# Emulator.net
KiCad netlist of a schematic drawn in EAGLE
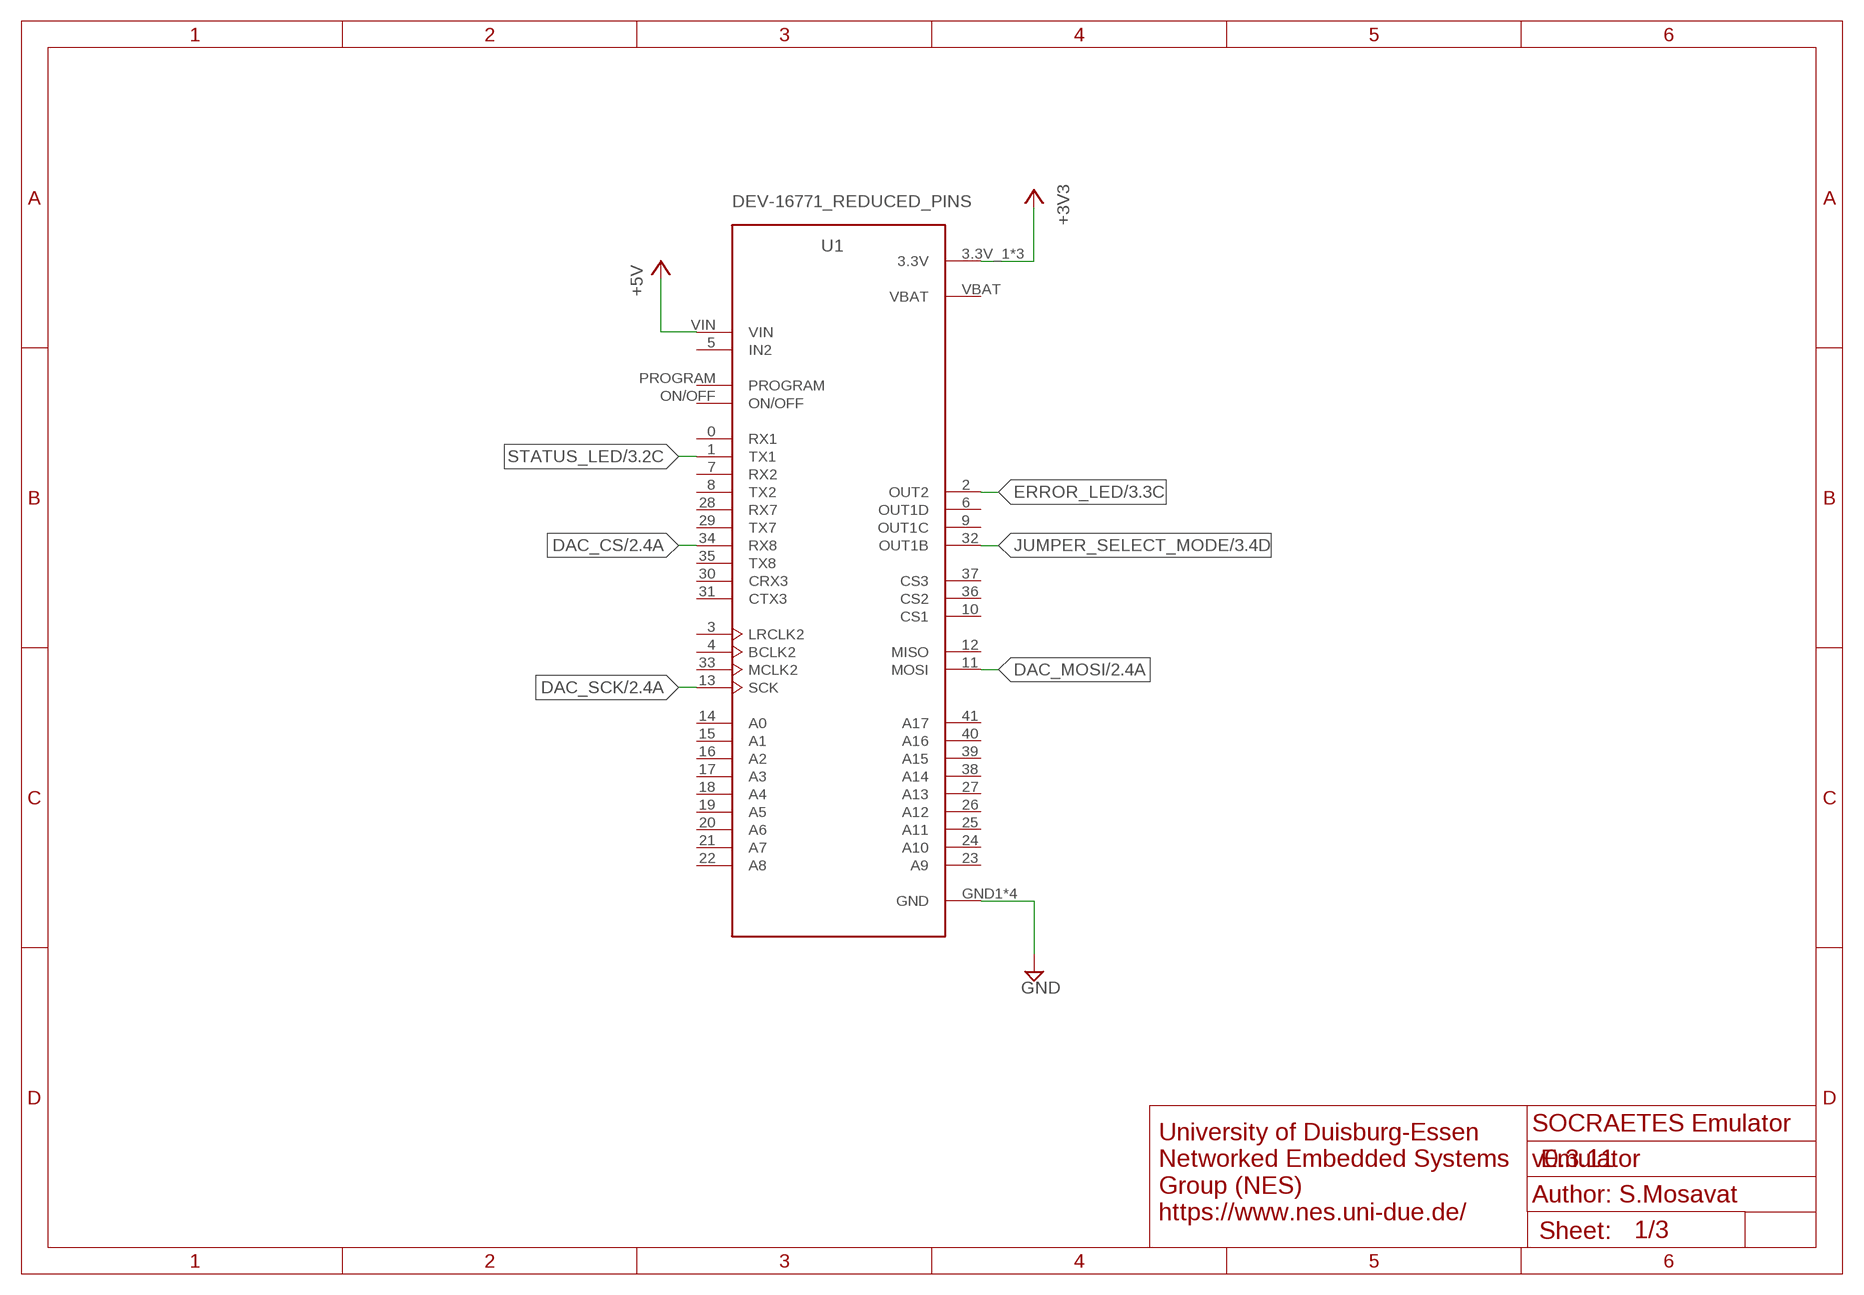
[diagram p0: schematic, sheet 1]
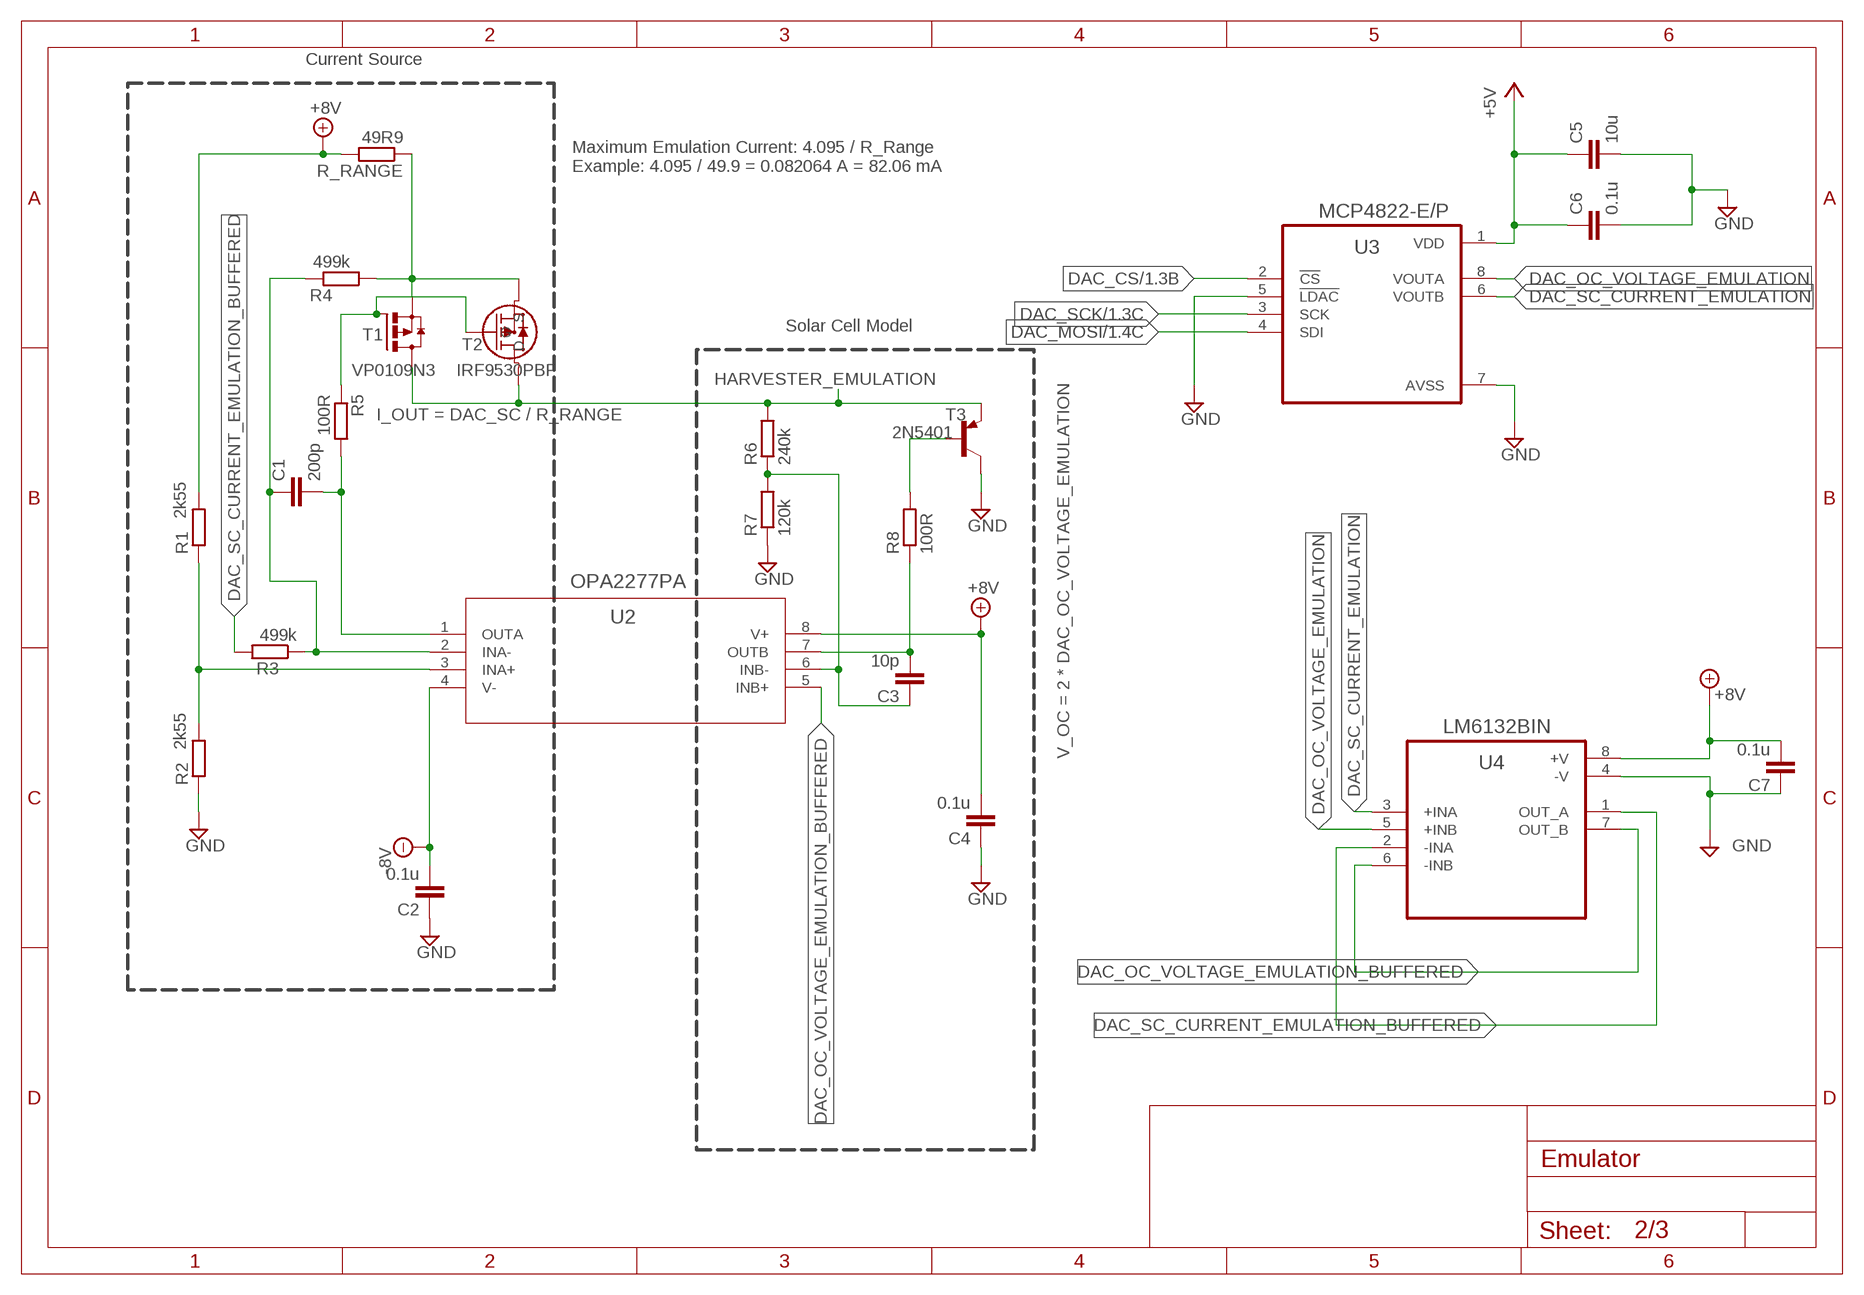
[diagram p1: schematic, sheet 2]
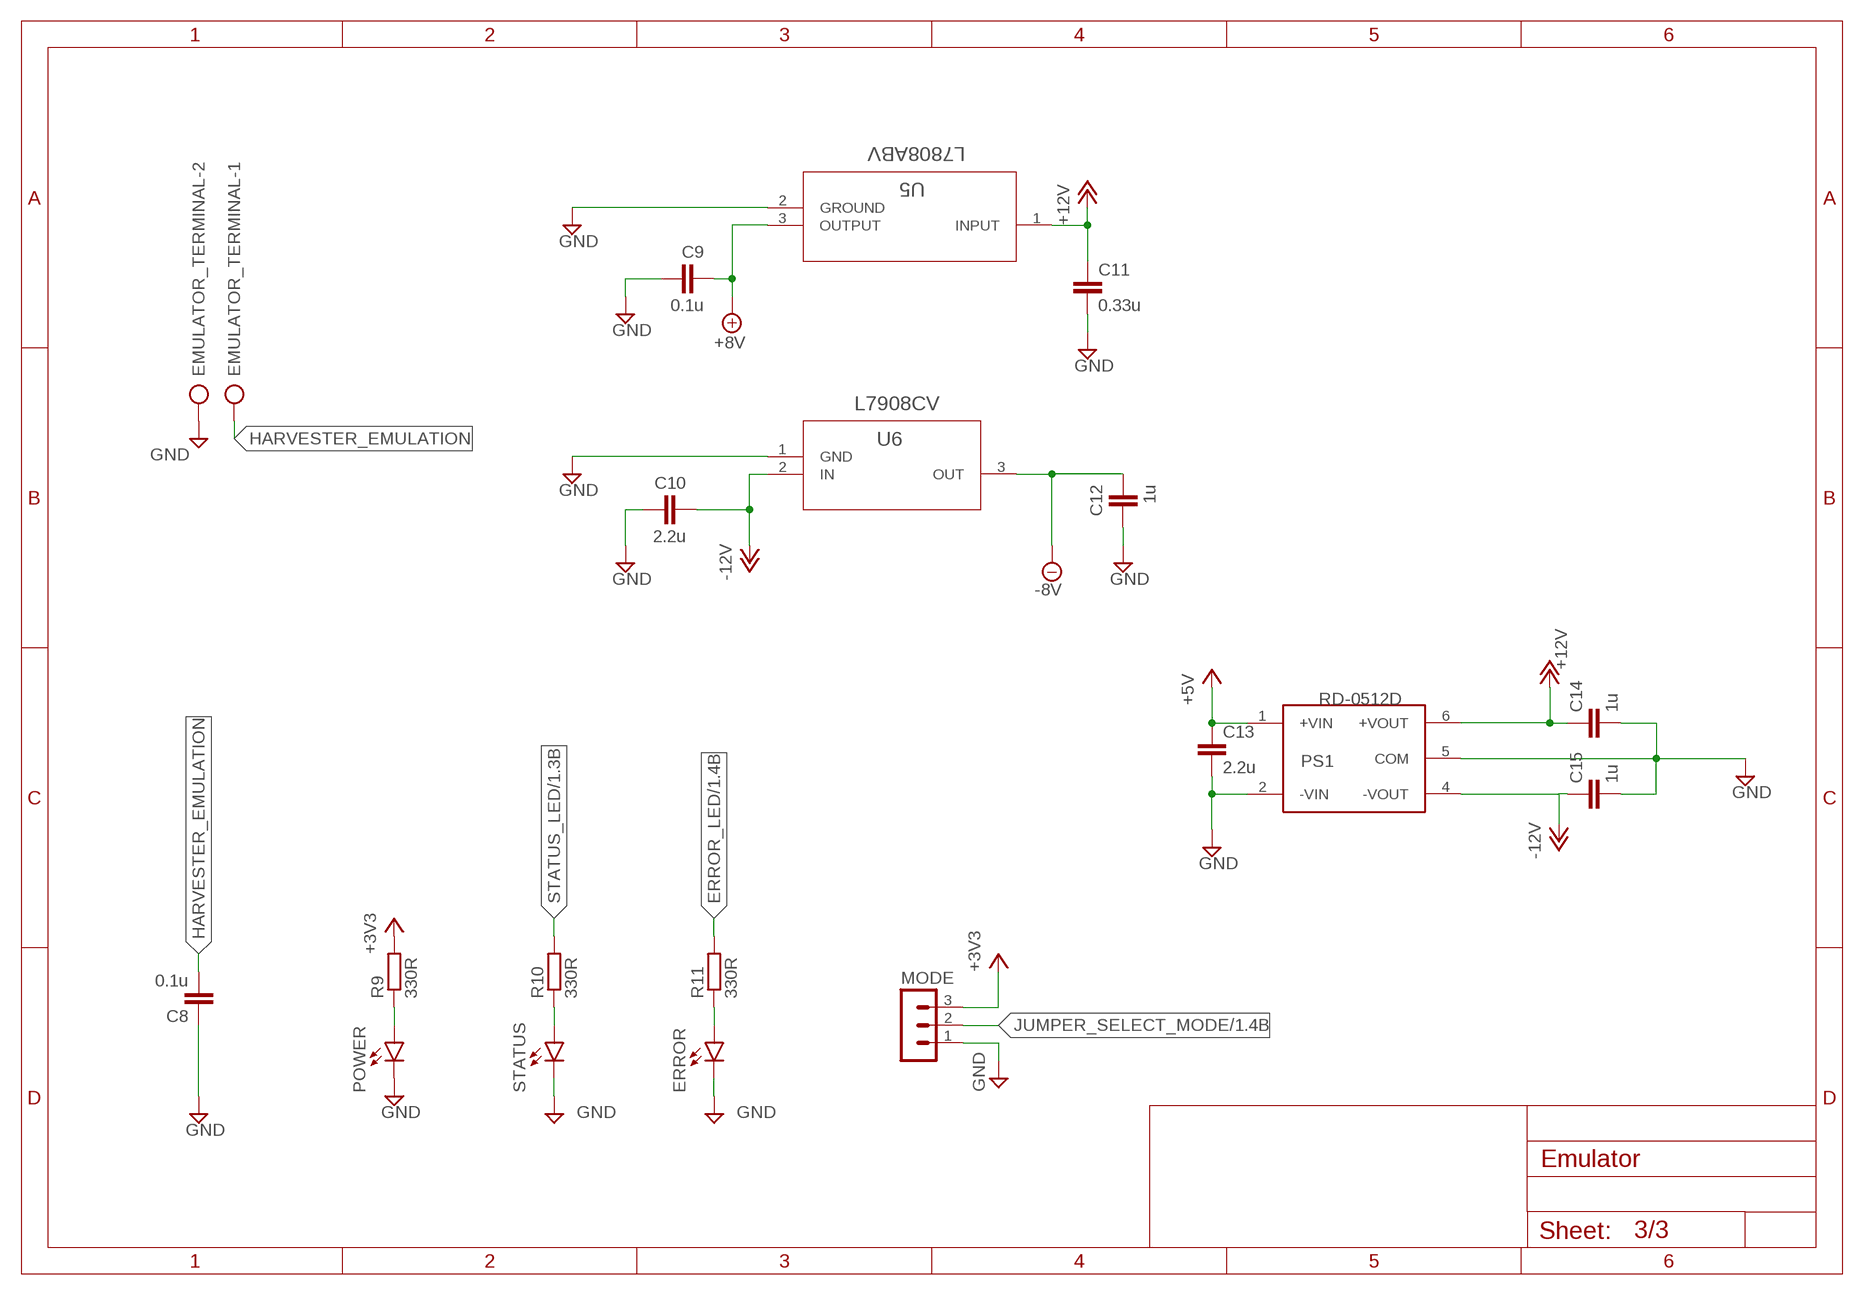
[diagram p2: schematic, sheet 3]

(export (version "E")
  (design (tool "Eeschema 10.0.6"))
  (components
    (comp (ref "U1")
      (value "DEV-16771_REDUCED_PINS")
      (footprint "eagle-import:MODULE_DEV-16771_REDUCED_PINS")
      (libsource (lib "eagle-import") (part "DEV-16771_REDUCED_PINS"))
    )
    (comp (ref "C1")
      (value "200p")
      (footprint "eagle-import:C025-024X044")
      (libsource (lib "eagle-import") (part "C-EU025-024X044"))
    )
    (comp (ref "C2")
      (value "0.1u")
      (footprint "eagle-import:C025-024X044")
      (libsource (lib "eagle-import") (part "C-EU025-024X044"))
    )
    (comp (ref "C3")
      (value "10p")
      (footprint "eagle-import:C025-024X044")
      (libsource (lib "eagle-import") (part "C-EU025-024X044"))
    )
    (comp (ref "C4")
      (value "0.1u")
      (footprint "eagle-import:C025-024X044")
      (libsource (lib "eagle-import") (part "C-EU025-024X044"))
    )
    (comp (ref "C5")
      (value "10u")
      (footprint "eagle-import:C025-024X044")
      (libsource (lib "eagle-import") (part "C-EU025-024X044"))
    )
    (comp (ref "C6")
      (value "0.1u")
      (footprint "eagle-import:C025-024X044")
      (libsource (lib "eagle-import") (part "C-EU025-024X044"))
    )
    (comp (ref "C7")
      (value "0.1u")
      (footprint "eagle-import:C025-024X044")
      (libsource (lib "eagle-import") (part "C-EU025-024X044"))
    )
    (comp (ref "R1")
      (value "2k55")
      (footprint "eagle-import:0207_10")
      (libsource (lib "eagle-import") (part "R-EU_0207/10"))
    )
    (comp (ref "R2")
      (value "2k55")
      (footprint "eagle-import:0207_10")
      (libsource (lib "eagle-import") (part "R-EU_0207/10"))
    )
    (comp (ref "R3")
      (value "499k")
      (footprint "eagle-import:0207_10")
      (libsource (lib "eagle-import") (part "R-EU_0207/10"))
    )
    (comp (ref "R4")
      (value "499k")
      (footprint "eagle-import:0207_10")
      (libsource (lib "eagle-import") (part "R-EU_0207/10"))
    )
    (comp (ref "R5")
      (value "100R")
      (footprint "eagle-import:0207_10")
      (libsource (lib "eagle-import") (part "R-EU_0207/10"))
    )
    (comp (ref "R6")
      (value "240k")
      (footprint "eagle-import:0207_10")
      (libsource (lib "eagle-import") (part "R-EU_0207/10"))
    )
    (comp (ref "R7")
      (value "120k")
      (footprint "eagle-import:0207_10")
      (libsource (lib "eagle-import") (part "R-EU_0207/10"))
    )
    (comp (ref "R8")
      (value "100R")
      (footprint "eagle-import:0207_10")
      (libsource (lib "eagle-import") (part "R-EU_0207/10"))
    )
    (comp (ref "R_RANGE")
      (value "49R9")
      (footprint "eagle-import:0207_10")
      (libsource (lib "eagle-import") (part "R-EU_0207/10"))
    )
    (comp (ref "T1")
      (value "VP0109N3")
      (footprint "eagle-import:TO92-SGD")
      (libsource (lib "eagle-import") (part "VP0109N3"))
    )
    (comp (ref "T2")
      (value "IRF9530PBF")
      (footprint "eagle-import:TO220AB_VIS")
      (fields (field (name "COPYRIGHT") "Copyright (C) 2023 Ultra Librarian. All rights reserved."))
      (libsource (lib "eagle-import") (part "IRF9530PBF"))
    )
    (comp (ref "T3")
      (value "2N5401")
      (footprint "eagle-import:TO92-EBC")
      (libsource (lib "eagle-import") (part "-PNP-TO92-EBC2N5401"))
    )
    (comp (ref "U2")
      (value "OPA2277PA")
      (footprint "eagle-import:P8")
      (fields
        (field (name "GENERIC_PART_NUMBER") "OPA2277")
        (field (name "MANUFACTURER") "Texas Instruments")
      )
      (libsource (lib "eagle-import") (part "OPA2277PA"))
    )
    (comp (ref "U3")
      (value "MCP4822-E/P")
      (footprint "eagle-import:DIP787W46P254L927H533Q8")
      (fields (field (name "MF") "Microchip"))
      (libsource (lib "eagle-import") (part "MCP4822-E/P"))
    )
    (comp (ref "U4")
      (value "LM6132BIN")
      (footprint "eagle-import:DIP794W45P254L959H508Q8")
      (fields
        (field (name "DIGI-KEY_PART_NUMBER") "LM6132BIN/NOPB-ND")
        (field (name "MF") "Texas Instruments")
        (field (name "MP") "LM6132BIN/NOPB")
      )
      (libsource (lib "eagle-import") (part "LM6132BIN"))
    )
    (comp (ref "C8")
      (value "0.1u")
      (footprint "eagle-import:C025-024X044")
      (libsource (lib "eagle-import") (part "C-EU025-024X044"))
    )
    (comp (ref "C9")
      (value "0.1u")
      (footprint "eagle-import:C025-024X044")
      (libsource (lib "eagle-import") (part "C-EU025-024X044"))
    )
    (comp (ref "C10")
      (value "2.2u")
      (footprint "eagle-import:C025-024X044")
      (libsource (lib "eagle-import") (part "C-EU025-024X044"))
    )
    (comp (ref "C11")
      (value "0.33u")
      (footprint "eagle-import:C025-024X044")
      (libsource (lib "eagle-import") (part "C-EU025-024X044"))
    )
    (comp (ref "C12")
      (value "1u")
      (footprint "eagle-import:C025-024X044")
      (libsource (lib "eagle-import") (part "C-EU025-024X044"))
    )
    (comp (ref "C13")
      (value "2.2u")
      (footprint "eagle-import:C025-024X044")
      (libsource (lib "eagle-import") (part "C-EU025-024X044"))
    )
    (comp (ref "C14")
      (value "1u")
      (footprint "eagle-import:C025-024X044")
      (libsource (lib "eagle-import") (part "C-EU025-024X044"))
    )
    (comp (ref "C15")
      (value "1u")
      (footprint "eagle-import:C025-024X044")
      (libsource (lib "eagle-import") (part "C-EU025-024X044"))
    )
    (comp (ref "EMULATOR_TERMINAL")
      (value "AK300/2")
      (footprint "eagle-import:AK300_2")
      (libsource (lib "eagle-import") (part "AK300/2"))
    )
    (comp (ref "ERROR")
      (value "LED5MM")
      (footprint "eagle-import:LED5MM")
      (libsource (lib "eagle-import") (part "LED5MM"))
    )
    (comp (ref "MODE")
      (value "MA03-1")
      (footprint "eagle-import:MA03-1")
      (libsource (lib "eagle-import") (part "MA03-1"))
    )
    (comp (ref "POWER")
      (value "LED5MM")
      (footprint "eagle-import:LED5MM")
      (libsource (lib "eagle-import") (part "LED5MM"))
    )
    (comp (ref "PS1")
      (value "RD-0512D")
      (footprint "eagle-import:CONV_RD-0512D")
      (fields (field (name "MF") "Recom Power"))
      (libsource (lib "eagle-import") (part "RD-0512D"))
    )
    (comp (ref "R9")
      (value "330R")
      (footprint "eagle-import:0207_10")
      (libsource (lib "eagle-import") (part "R-EU_0207/10"))
    )
    (comp (ref "R10")
      (value "330R")
      (footprint "eagle-import:0207_10")
      (libsource (lib "eagle-import") (part "R-EU_0207/10"))
    )
    (comp (ref "R11")
      (value "330R")
      (footprint "eagle-import:0207_10")
      (libsource (lib "eagle-import") (part "R-EU_0207/10"))
    )
    (comp (ref "STATUS")
      (value "LED5MM")
      (footprint "eagle-import:LED5MM")
      (libsource (lib "eagle-import") (part "LED5MM"))
    )
    (comp (ref "U5")
      (value "L7808ABV")
      (footprint "eagle-import:TO-220_STM")
      (libsource (lib "eagle-import") (part "L7808ABV"))
    )
    (comp (ref "U6")
      (value "L7908CV")
      (footprint "eagle-import:TO-220_STM")
      (libsource (lib "eagle-import") (part "L7908CV"))
    )
  )
  (nets
    (net (code "1") (name "+3V3") (class "Default")
      (node (ref "MODE") (pin "3") (pinfunction "3_3") (pintype "passive"))
      (node (ref "R9") (pin "2") (pinfunction "2_2") (pintype "passive"))
      (node (ref "U1") (pin "3.3V_1") (pinfunction "3.3V_3.3V_1") (pintype "power_in"))
      (node (ref "U1") (pin "3.3V_2") (pinfunction "3.3V_3.3V_2") (pintype "power_in"))
      (node (ref "U1") (pin "3.3V_3") (pinfunction "3.3V_3.3V_3") (pintype "power_in"))
    )
    (net (code "2") (name "+5V") (class "Default")
      (node (ref "C13") (pin "1") (pinfunction "1_1") (pintype "passive"))
      (node (ref "C5") (pin "1") (pinfunction "1_1") (pintype "passive"))
      (node (ref "C6") (pin "1") (pinfunction "1_1") (pintype "passive"))
      (node (ref "PS1") (pin "1") (pinfunction "+VIN_1") (pintype "input"))
      (node (ref "U1") (pin "VIN") (pinfunction "VIN_VIN") (pintype "input"))
      (node (ref "U3") (pin "1") (pinfunction "VDD_1") (pintype "power_in"))
    )
    (net (code "3") (name "+8V") (class "Default")
      (node (ref "C4") (pin "2") (pinfunction "2_2") (pintype "passive"))
      (node (ref "C7") (pin "2") (pinfunction "2_2") (pintype "passive"))
      (node (ref "C9") (pin "2") (pinfunction "2_2") (pintype "passive"))
      (node (ref "R1") (pin "2") (pinfunction "2_2") (pintype "passive"))
      (node (ref "R_RANGE") (pin "2") (pinfunction "2_2") (pintype "passive"))
      (node (ref "U2") (pin "8") (pinfunction "V+_8") (pintype "power_in"))
      (node (ref "U4") (pin "8") (pinfunction "+V_8") (pintype "power_in"))
      (node (ref "U5") (pin "3") (pinfunction "OUTPUT_3") (pintype "output"))
    )
    (net (code "4") (name "+12V") (class "Default")
      (node (ref "C11") (pin "1") (pinfunction "1_1") (pintype "passive"))
      (node (ref "C14") (pin "1") (pinfunction "1_1") (pintype "passive"))
      (node (ref "PS1") (pin "6") (pinfunction "+VOUT_6") (pintype "output"))
      (node (ref "U5") (pin "1") (pinfunction "INPUT_1") (pintype "input"))
    )
    (net (code "5") (name "-8V") (class "Default")
      (node (ref "C12") (pin "2") (pinfunction "2_2") (pintype "passive"))
      (node (ref "C2") (pin "2") (pinfunction "2_2") (pintype "passive"))
      (node (ref "U2") (pin "4") (pinfunction "V-_4") (pintype "power_in"))
      (node (ref "U6") (pin "3") (pinfunction "OUT_3") (pintype "power_in"))
    )
    (net (code "6") (name "-12V") (class "Default")
      (node (ref "C10") (pin "2") (pinfunction "2_2") (pintype "passive"))
      (node (ref "C15") (pin "1") (pinfunction "1_1") (pintype "passive"))
      (node (ref "PS1") (pin "4") (pinfunction "-VOUT_4") (pintype "output"))
      (node (ref "U6") (pin "2") (pinfunction "IN_2") (pintype "power_in"))
    )
    (net (code "7") (name "DAC_CS") (class "Default")
      (node (ref "U1") (pin "34") (pinfunction "RX8_34") (pintype "bidirectional"))
      (node (ref "U3") (pin "2") (pinfunction "~{CS}_2") (pintype "input"))
    )
    (net (code "8") (name "DAC_MOSI") (class "Default")
      (node (ref "U1") (pin "11") (pinfunction "MOSI_11") (pintype "bidirectional"))
      (node (ref "U3") (pin "4") (pinfunction "SDI_4") (pintype "input"))
    )
    (net (code "9") (name "DAC_OC_VOLTAGE_EMULATION") (class "Default")
      (node (ref "U3") (pin "8") (pinfunction "VOUTA_8") (pintype "output"))
      (node (ref "U4") (pin "5") (pinfunction "+INB_5") (pintype "input"))
    )
    (net (code "10") (name "DAC_OC_VOLTAGE_EMULATION_BUFFERED") (class "Default")
      (node (ref "U2") (pin "5") (pinfunction "INB+_5") (pintype "input"))
      (node (ref "U4") (pin "6") (pinfunction "-INB_6") (pintype "input"))
      (node (ref "U4") (pin "7") (pinfunction "OUT_B_7") (pintype "output"))
    )
    (net (code "11") (name "DAC_SCK") (class "Default")
      (node (ref "U1") (pin "13") (pinfunction "SCK_13") (pintype "bidirectional"))
      (node (ref "U3") (pin "3") (pinfunction "SCK_3") (pintype "input"))
    )
    (net (code "12") (name "DAC_SC_CURRENT_EMULATION") (class "Default")
      (node (ref "U3") (pin "6") (pinfunction "VOUTB_6") (pintype "output"))
      (node (ref "U4") (pin "3") (pinfunction "+INA_3") (pintype "input"))
    )
    (net (code "13") (name "DAC_SC_CURRENT_EMULATION_BUFFERED") (class "Default")
      (node (ref "R3") (pin "2") (pinfunction "2_2") (pintype "passive"))
      (node (ref "U4") (pin "1") (pinfunction "OUT_A_1") (pintype "output"))
      (node (ref "U4") (pin "2") (pinfunction "-INA_2") (pintype "input"))
    )
    (net (code "14") (name "ERROR_LED") (class "Default")
      (node (ref "R11") (pin "2") (pinfunction "2_2") (pintype "passive"))
      (node (ref "U1") (pin "2") (pinfunction "OUT2_2") (pintype "output"))
    )
    (net (code "15") (name "GND") (class "Default")
      (node (ref "C10") (pin "1") (pinfunction "1_1") (pintype "passive"))
      (node (ref "C11") (pin "2") (pinfunction "2_2") (pintype "passive"))
      (node (ref "C12") (pin "1") (pinfunction "1_1") (pintype "passive"))
      (node (ref "C13") (pin "2") (pinfunction "2_2") (pintype "passive"))
      (node (ref "C14") (pin "2") (pinfunction "2_2") (pintype "passive"))
      (node (ref "C15") (pin "2") (pinfunction "2_2") (pintype "passive"))
      (node (ref "C2") (pin "1") (pinfunction "1_1") (pintype "passive"))
      (node (ref "C4") (pin "1") (pinfunction "1_1") (pintype "passive"))
      (node (ref "C5") (pin "2") (pinfunction "2_2") (pintype "passive"))
      (node (ref "C6") (pin "2") (pinfunction "2_2") (pintype "passive"))
      (node (ref "C7") (pin "1") (pinfunction "1_1") (pintype "passive"))
      (node (ref "C8") (pin "1") (pinfunction "1_1") (pintype "passive"))
      (node (ref "C9") (pin "1") (pinfunction "1_1") (pintype "passive"))
      (node (ref "EMULATOR_TERMINAL") (pin "2") (pinfunction "KL_2") (pintype "passive"))
      (node (ref "ERROR") (pin "K") (pinfunction "C_K") (pintype "passive"))
      (node (ref "MODE") (pin "1") (pinfunction "1_1") (pintype "passive"))
      (node (ref "POWER") (pin "K") (pinfunction "C_K") (pintype "passive"))
      (node (ref "PS1") (pin "2") (pinfunction "-VIN_2") (pintype "input"))
      (node (ref "PS1") (pin "5") (pinfunction "COM_5") (pintype "power_in"))
      (node (ref "R2") (pin "1") (pinfunction "1_1") (pintype "passive"))
      (node (ref "R7") (pin "1") (pinfunction "1_1") (pintype "passive"))
      (node (ref "STATUS") (pin "K") (pinfunction "C_K") (pintype "passive"))
      (node (ref "T3") (pin "C") (pinfunction "C_C") (pintype "passive"))
      (node (ref "U1") (pin "GND1") (pinfunction "GND_GND1") (pintype "power_in"))
      (node (ref "U1") (pin "GND2") (pinfunction "GND_GND2") (pintype "power_in"))
      (node (ref "U1") (pin "GND3") (pinfunction "GND_GND3") (pintype "power_in"))
      (node (ref "U1") (pin "GND4") (pinfunction "GND_GND4") (pintype "power_in"))
      (node (ref "U3") (pin "5") (pinfunction "~{LDAC}_5") (pintype "input"))
      (node (ref "U3") (pin "7") (pinfunction "AVSS_7") (pintype "power_in"))
      (node (ref "U4") (pin "4") (pinfunction "-V_4") (pintype "power_in"))
      (node (ref "U5") (pin "2") (pinfunction "GROUND_2") (pintype "passive"))
      (node (ref "U6") (pin "1") (pinfunction "GND_1") (pintype "power_in"))
    )
    (net (code "16") (name "HARVESTER_EMULATION") (class "Default")
      (node (ref "C8") (pin "2") (pinfunction "2_2") (pintype "passive"))
      (node (ref "EMULATOR_TERMINAL") (pin "1") (pinfunction "KL_1") (pintype "passive"))
      (node (ref "R6") (pin "2") (pinfunction "2_2") (pintype "passive"))
      (node (ref "T1") (pin "DRAIN") (pinfunction "D_DRAIN") (pintype "passive"))
      (node (ref "T2") (pin "D") (pinfunction "D_D") (pintype "passive"))
      (node (ref "T3") (pin "E") (pinfunction "E_E") (pintype "passive"))
    )
    (net (code "17") (name "JUMPER_SELECT_MODE") (class "Default")
      (node (ref "MODE") (pin "2") (pinfunction "2_2") (pintype "passive"))
      (node (ref "U1") (pin "32") (pinfunction "OUT1B_32") (pintype "output"))
    )
    (net (code "18") (name "Net-(ERROR-PadA)") (class "Default")
      (node (ref "ERROR") (pin "A") (pinfunction "A_A") (pintype "passive"))
      (node (ref "R11") (pin "1") (pinfunction "1_1") (pintype "passive"))
    )
    (net (code "19") (name "Net-(POWER-PadA)") (class "Default")
      (node (ref "POWER") (pin "A") (pinfunction "A_A") (pintype "passive"))
      (node (ref "R9") (pin "1") (pinfunction "1_1") (pintype "passive"))
    )
    (net (code "20") (name "Net-(R8-Pad2)") (class "Default")
      (node (ref "R8") (pin "2") (pinfunction "2_2") (pintype "passive"))
      (node (ref "T3") (pin "B") (pinfunction "B_B") (pintype "passive"))
    )
    (net (code "21") (name "Net-(R10-Pad1)") (class "Default")
      (node (ref "R10") (pin "1") (pinfunction "1_1") (pintype "passive"))
      (node (ref "STATUS") (pin "A") (pinfunction "A_A") (pintype "passive"))
    )
    (net (code "22") (name "Net-(T1-G)") (class "Default")
      (node (ref "R5") (pin "1") (pinfunction "1_1") (pintype "passive"))
      (node (ref "T1") (pin "GATE") (pinfunction "G_GATE") (pintype "passive"))
      (node (ref "T2") (pin "G") (pinfunction "G_G") (pintype "passive"))
    )
    (net (code "23") (name "Net-(T1-S)") (class "Default")
      (node (ref "R4") (pin "1") (pinfunction "1_1") (pintype "passive"))
      (node (ref "R_RANGE") (pin "1") (pinfunction "1_1") (pintype "passive"))
      (node (ref "T1") (pin "SOURCE") (pinfunction "S_SOURCE") (pintype "passive"))
      (node (ref "T2") (pin "S") (pinfunction "S_S") (pintype "passive"))
    )
    (net (code "24") (name "Net-(U2-INA+)") (class "Default")
      (node (ref "R1") (pin "1") (pinfunction "1_1") (pintype "passive"))
      (node (ref "R2") (pin "2") (pinfunction "2_2") (pintype "passive"))
      (node (ref "U2") (pin "3") (pinfunction "INA+_3") (pintype "input"))
    )
    (net (code "25") (name "Net-(U2-INA-)") (class "Default")
      (node (ref "C1") (pin "1") (pinfunction "1_1") (pintype "passive"))
      (node (ref "R3") (pin "1") (pinfunction "1_1") (pintype "passive"))
      (node (ref "R4") (pin "2") (pinfunction "2_2") (pintype "passive"))
      (node (ref "U2") (pin "2") (pinfunction "INA-_2") (pintype "input"))
    )
    (net (code "26") (name "Net-(U2-INB-)") (class "Default")
      (node (ref "C3") (pin "1") (pinfunction "1_1") (pintype "passive"))
      (node (ref "R6") (pin "1") (pinfunction "1_1") (pintype "passive"))
      (node (ref "R7") (pin "2") (pinfunction "2_2") (pintype "passive"))
      (node (ref "U2") (pin "6") (pinfunction "INB-_6") (pintype "input"))
    )
    (net (code "27") (name "Net-(U2-OUTA)") (class "Default")
      (node (ref "C1") (pin "2") (pinfunction "2_2") (pintype "passive"))
      (node (ref "R5") (pin "2") (pinfunction "2_2") (pintype "passive"))
      (node (ref "U2") (pin "1") (pinfunction "OUTA_1") (pintype "output"))
    )
    (net (code "28") (name "Net-(U2-OUTB)") (class "Default")
      (node (ref "C3") (pin "2") (pinfunction "2_2") (pintype "passive"))
      (node (ref "R8") (pin "1") (pinfunction "1_1") (pintype "passive"))
      (node (ref "U2") (pin "7") (pinfunction "OUTB_7") (pintype "output"))
    )
    (net (code "29") (name "STATUS_LED") (class "Default")
      (node (ref "R10") (pin "2") (pinfunction "2_2") (pintype "passive"))
      (node (ref "U1") (pin "1") (pinfunction "TX1_1") (pintype "bidirectional"))
    )
    (net (code "30") (name "unconnected-(U1-A0-Pad14)") (class "Default")
      (node (ref "U1") (pin "14") (pinfunction "A0_14") (pintype "bidirectional"))
    )
    (net (code "31") (name "unconnected-(U1-A1-Pad15)") (class "Default")
      (node (ref "U1") (pin "15") (pinfunction "A1_15") (pintype "bidirectional"))
    )
    (net (code "32") (name "unconnected-(U1-A2-Pad16)") (class "Default")
      (node (ref "U1") (pin "16") (pinfunction "A2_16") (pintype "bidirectional"))
    )
    (net (code "33") (name "unconnected-(U1-A3-Pad17)") (class "Default")
      (node (ref "U1") (pin "17") (pinfunction "A3_17") (pintype "bidirectional"))
    )
    (net (code "34") (name "unconnected-(U1-A4-Pad18)") (class "Default")
      (node (ref "U1") (pin "18") (pinfunction "A4_18") (pintype "bidirectional"))
    )
    (net (code "35") (name "unconnected-(U1-A5-Pad19)") (class "Default")
      (node (ref "U1") (pin "19") (pinfunction "A5_19") (pintype "bidirectional"))
    )
    (net (code "36") (name "unconnected-(U1-A6-Pad20)") (class "Default")
      (node (ref "U1") (pin "20") (pinfunction "A6_20") (pintype "bidirectional"))
    )
    (net (code "37") (name "unconnected-(U1-A7-Pad21)") (class "Default")
      (node (ref "U1") (pin "21") (pinfunction "A7_21") (pintype "bidirectional"))
    )
    (net (code "38") (name "unconnected-(U1-A8-Pad22)") (class "Default")
      (node (ref "U1") (pin "22") (pinfunction "A8_22") (pintype "bidirectional"))
    )
    (net (code "39") (name "unconnected-(U1-A9-Pad23)") (class "Default")
      (node (ref "U1") (pin "23") (pinfunction "A9_23") (pintype "bidirectional"))
    )
    (net (code "40") (name "unconnected-(U1-A10-Pad24)") (class "Default")
      (node (ref "U1") (pin "24") (pinfunction "A10_24") (pintype "bidirectional"))
    )
    (net (code "41") (name "unconnected-(U1-A11-Pad25)") (class "Default")
      (node (ref "U1") (pin "25") (pinfunction "A11_25") (pintype "bidirectional"))
    )
    (net (code "42") (name "unconnected-(U1-A12-Pad26)") (class "Default")
      (node (ref "U1") (pin "26") (pinfunction "A12_26") (pintype "bidirectional"))
    )
    (net (code "43") (name "unconnected-(U1-A13-Pad27)") (class "Default")
      (node (ref "U1") (pin "27") (pinfunction "A13_27") (pintype "bidirectional"))
    )
    (net (code "44") (name "unconnected-(U1-A14-Pad38)") (class "Default")
      (node (ref "U1") (pin "38") (pinfunction "A14_38") (pintype "bidirectional"))
    )
    (net (code "45") (name "unconnected-(U1-A15-Pad39)") (class "Default")
      (node (ref "U1") (pin "39") (pinfunction "A15_39") (pintype "bidirectional"))
    )
    (net (code "46") (name "unconnected-(U1-A16-Pad40)") (class "Default")
      (node (ref "U1") (pin "40") (pinfunction "A16_40") (pintype "bidirectional"))
    )
    (net (code "47") (name "unconnected-(U1-A17-Pad41)") (class "Default")
      (node (ref "U1") (pin "41") (pinfunction "A17_41") (pintype "bidirectional"))
    )
    (net (code "48") (name "unconnected-(U1-BCLK2-Pad4)") (class "Default")
      (node (ref "U1") (pin "4") (pinfunction "BCLK2_4") (pintype "bidirectional"))
    )
    (net (code "49") (name "unconnected-(U1-CRX3-Pad30)") (class "Default")
      (node (ref "U1") (pin "30") (pinfunction "CRX3_30") (pintype "bidirectional"))
    )
    (net (code "50") (name "unconnected-(U1-CS1-Pad10)") (class "Default")
      (node (ref "U1") (pin "10") (pinfunction "CS1_10") (pintype "bidirectional"))
    )
    (net (code "51") (name "unconnected-(U1-CS2-Pad36)") (class "Default")
      (node (ref "U1") (pin "36") (pinfunction "CS2_36") (pintype "bidirectional"))
    )
    (net (code "52") (name "unconnected-(U1-CS3-Pad37)") (class "Default")
      (node (ref "U1") (pin "37") (pinfunction "CS3_37") (pintype "bidirectional"))
    )
    (net (code "53") (name "unconnected-(U1-CTX3-Pad31)") (class "Default")
      (node (ref "U1") (pin "31") (pinfunction "CTX3_31") (pintype "bidirectional"))
    )
    (net (code "54") (name "unconnected-(U1-IN2-Pad5)") (class "Default")
      (node (ref "U1") (pin "5") (pinfunction "IN2_5") (pintype "bidirectional"))
    )
    (net (code "55") (name "unconnected-(U1-LRCLK2-Pad3)") (class "Default")
      (node (ref "U1") (pin "3") (pinfunction "LRCLK2_3") (pintype "bidirectional"))
    )
    (net (code "56") (name "unconnected-(U1-MCLK2-Pad33)") (class "Default")
      (node (ref "U1") (pin "33") (pinfunction "MCLK2_33") (pintype "bidirectional"))
    )
    (net (code "57") (name "unconnected-(U1-MISO-Pad12)") (class "Default")
      (node (ref "U1") (pin "12") (pinfunction "MISO_12") (pintype "bidirectional"))
    )
    (net (code "58") (name "unconnected-(U1-OUT1C-Pad9)") (class "Default")
      (node (ref "U1") (pin "9") (pinfunction "OUT1C_9") (pintype "output"))
    )
    (net (code "59") (name "unconnected-(U1-OUT1D-Pad6)") (class "Default")
      (node (ref "U1") (pin "6") (pinfunction "OUT1D_6") (pintype "output"))
    )
    (net (code "60") (name "unconnected-(U1-PadON{slash}OFF)") (class "Default")
      (node (ref "U1") (pin "ON/OFF") (pinfunction "ON/OFF_ON/OFF") (pintype "bidirectional"))
    )
    (net (code "61") (name "unconnected-(U1-PadPROGRAM)") (class "Default")
      (node (ref "U1") (pin "PROGRAM") (pinfunction "PROGRAM_PROGRAM") (pintype "bidirectional"))
    )
    (net (code "62") (name "unconnected-(U1-PadVBAT)") (class "Default")
      (node (ref "U1") (pin "VBAT") (pinfunction "VBAT_VBAT") (pintype "passive"))
    )
    (net (code "63") (name "unconnected-(U1-RX1-Pad0)") (class "Default")
      (node (ref "U1") (pin "0") (pinfunction "RX1_0") (pintype "bidirectional"))
    )
    (net (code "64") (name "unconnected-(U1-RX2-Pad7)") (class "Default")
      (node (ref "U1") (pin "7") (pinfunction "RX2_7") (pintype "bidirectional"))
    )
    (net (code "65") (name "unconnected-(U1-RX7-Pad28)") (class "Default")
      (node (ref "U1") (pin "28") (pinfunction "RX7_28") (pintype "bidirectional"))
    )
    (net (code "66") (name "unconnected-(U1-TX2-Pad8)") (class "Default")
      (node (ref "U1") (pin "8") (pinfunction "TX2_8") (pintype "bidirectional"))
    )
    (net (code "67") (name "unconnected-(U1-TX7-Pad29)") (class "Default")
      (node (ref "U1") (pin "29") (pinfunction "TX7_29") (pintype "bidirectional"))
    )
    (net (code "68") (name "unconnected-(U1-TX8-Pad35)") (class "Default")
      (node (ref "U1") (pin "35") (pinfunction "TX8_35") (pintype "bidirectional"))
    )
  )
)
